# baby_monitor_v0.net
KiCad netlist of a schematic drawn in EAGLE
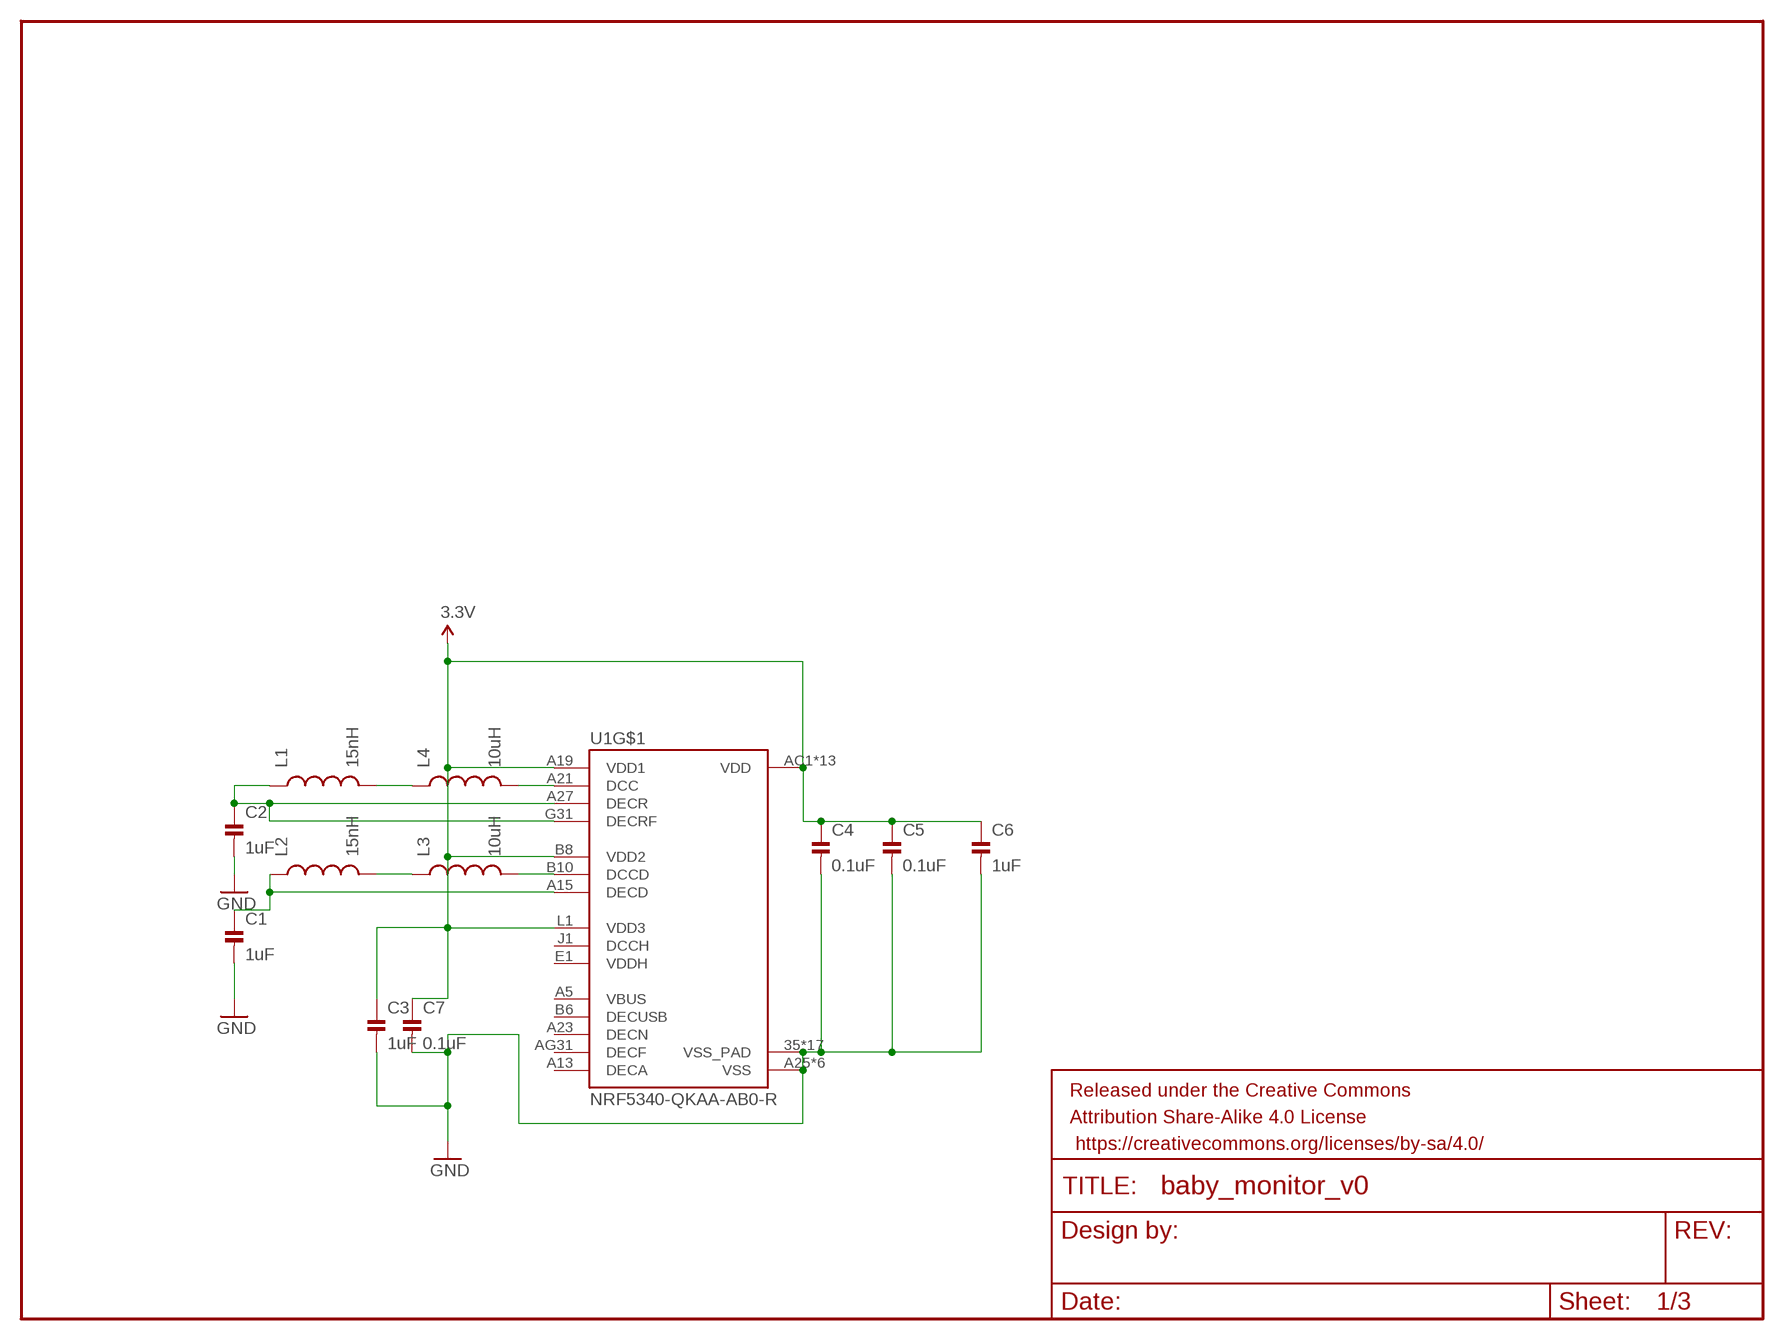
[diagram p0: schematic, sheet 1]
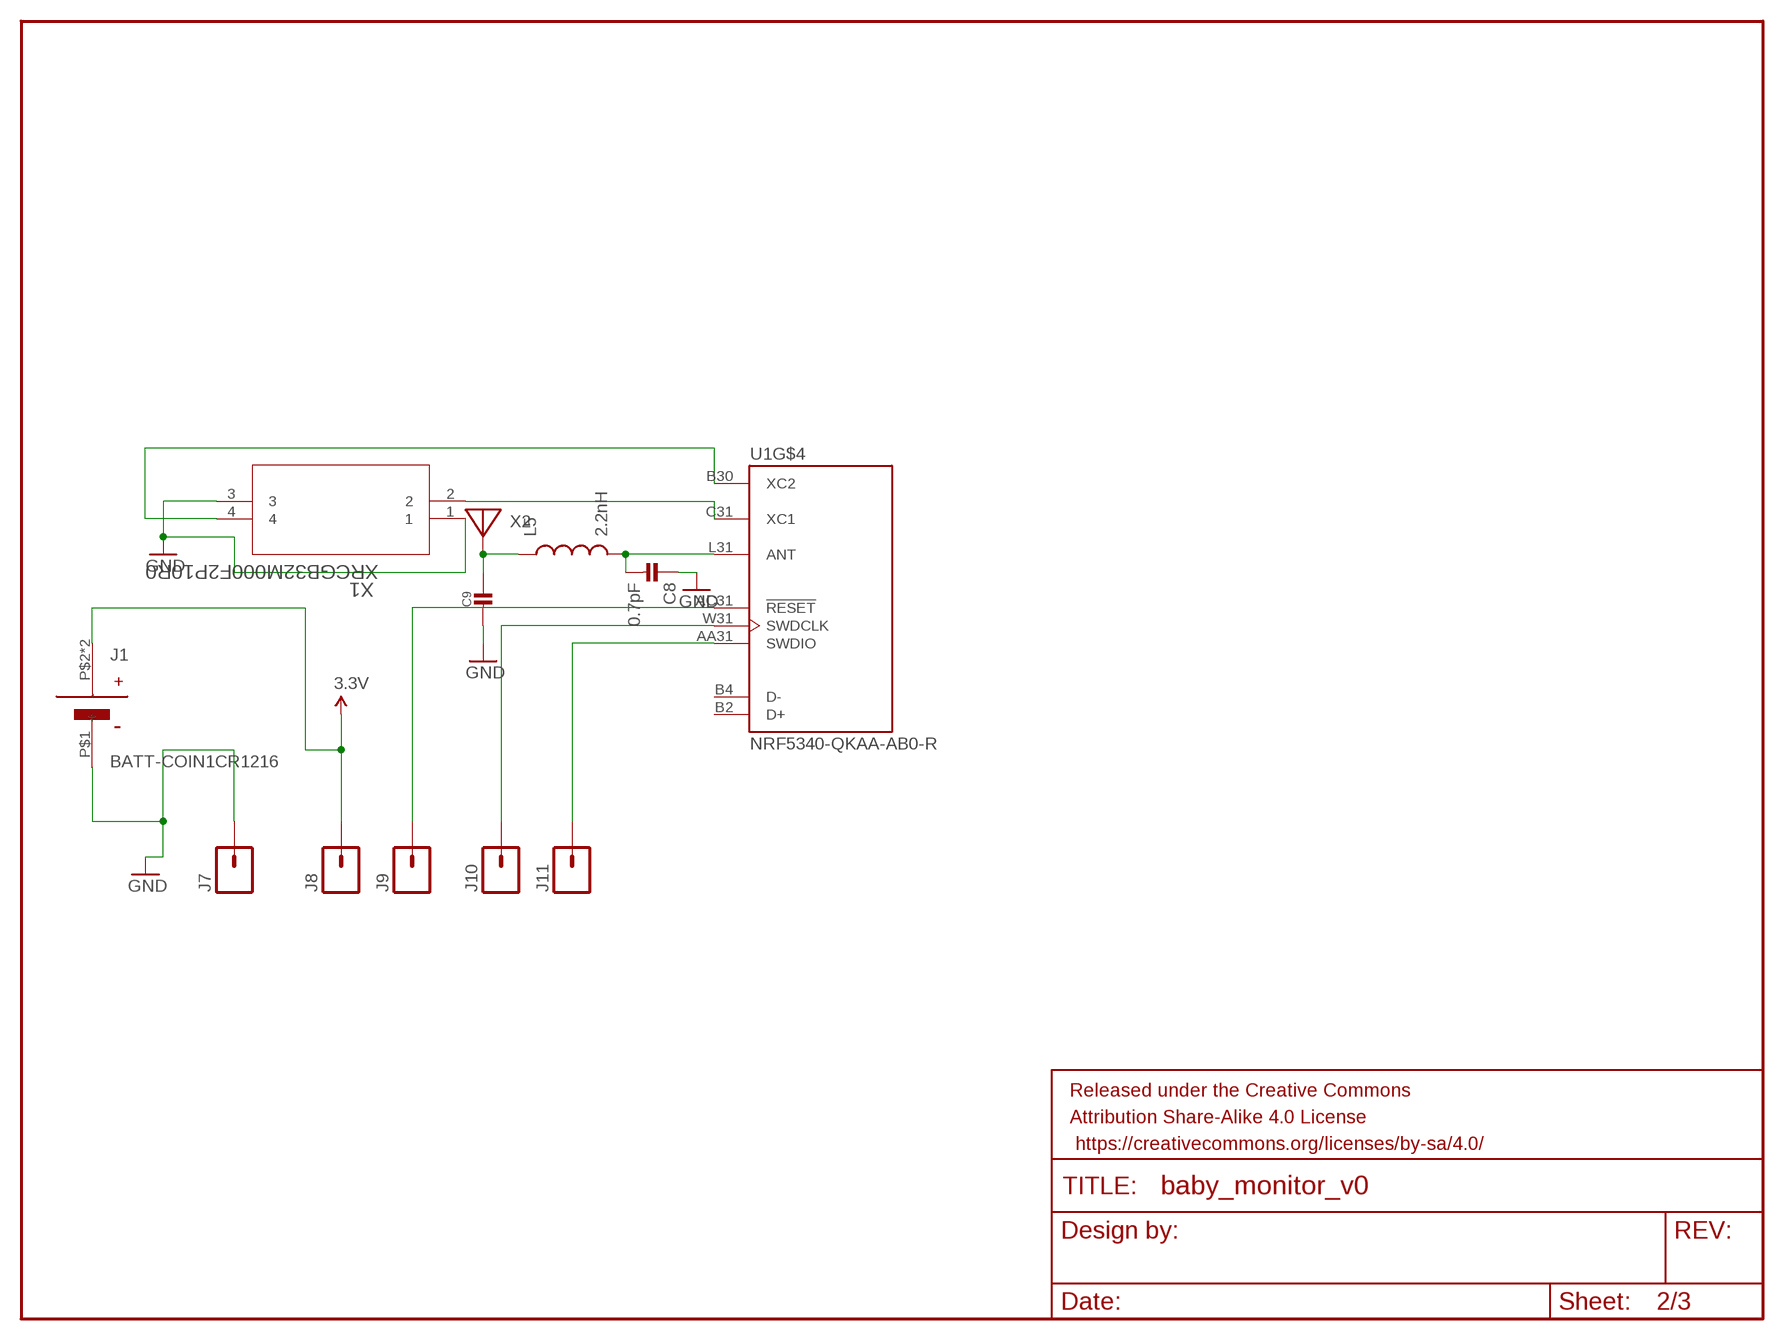
[diagram p1: schematic, sheet 2]
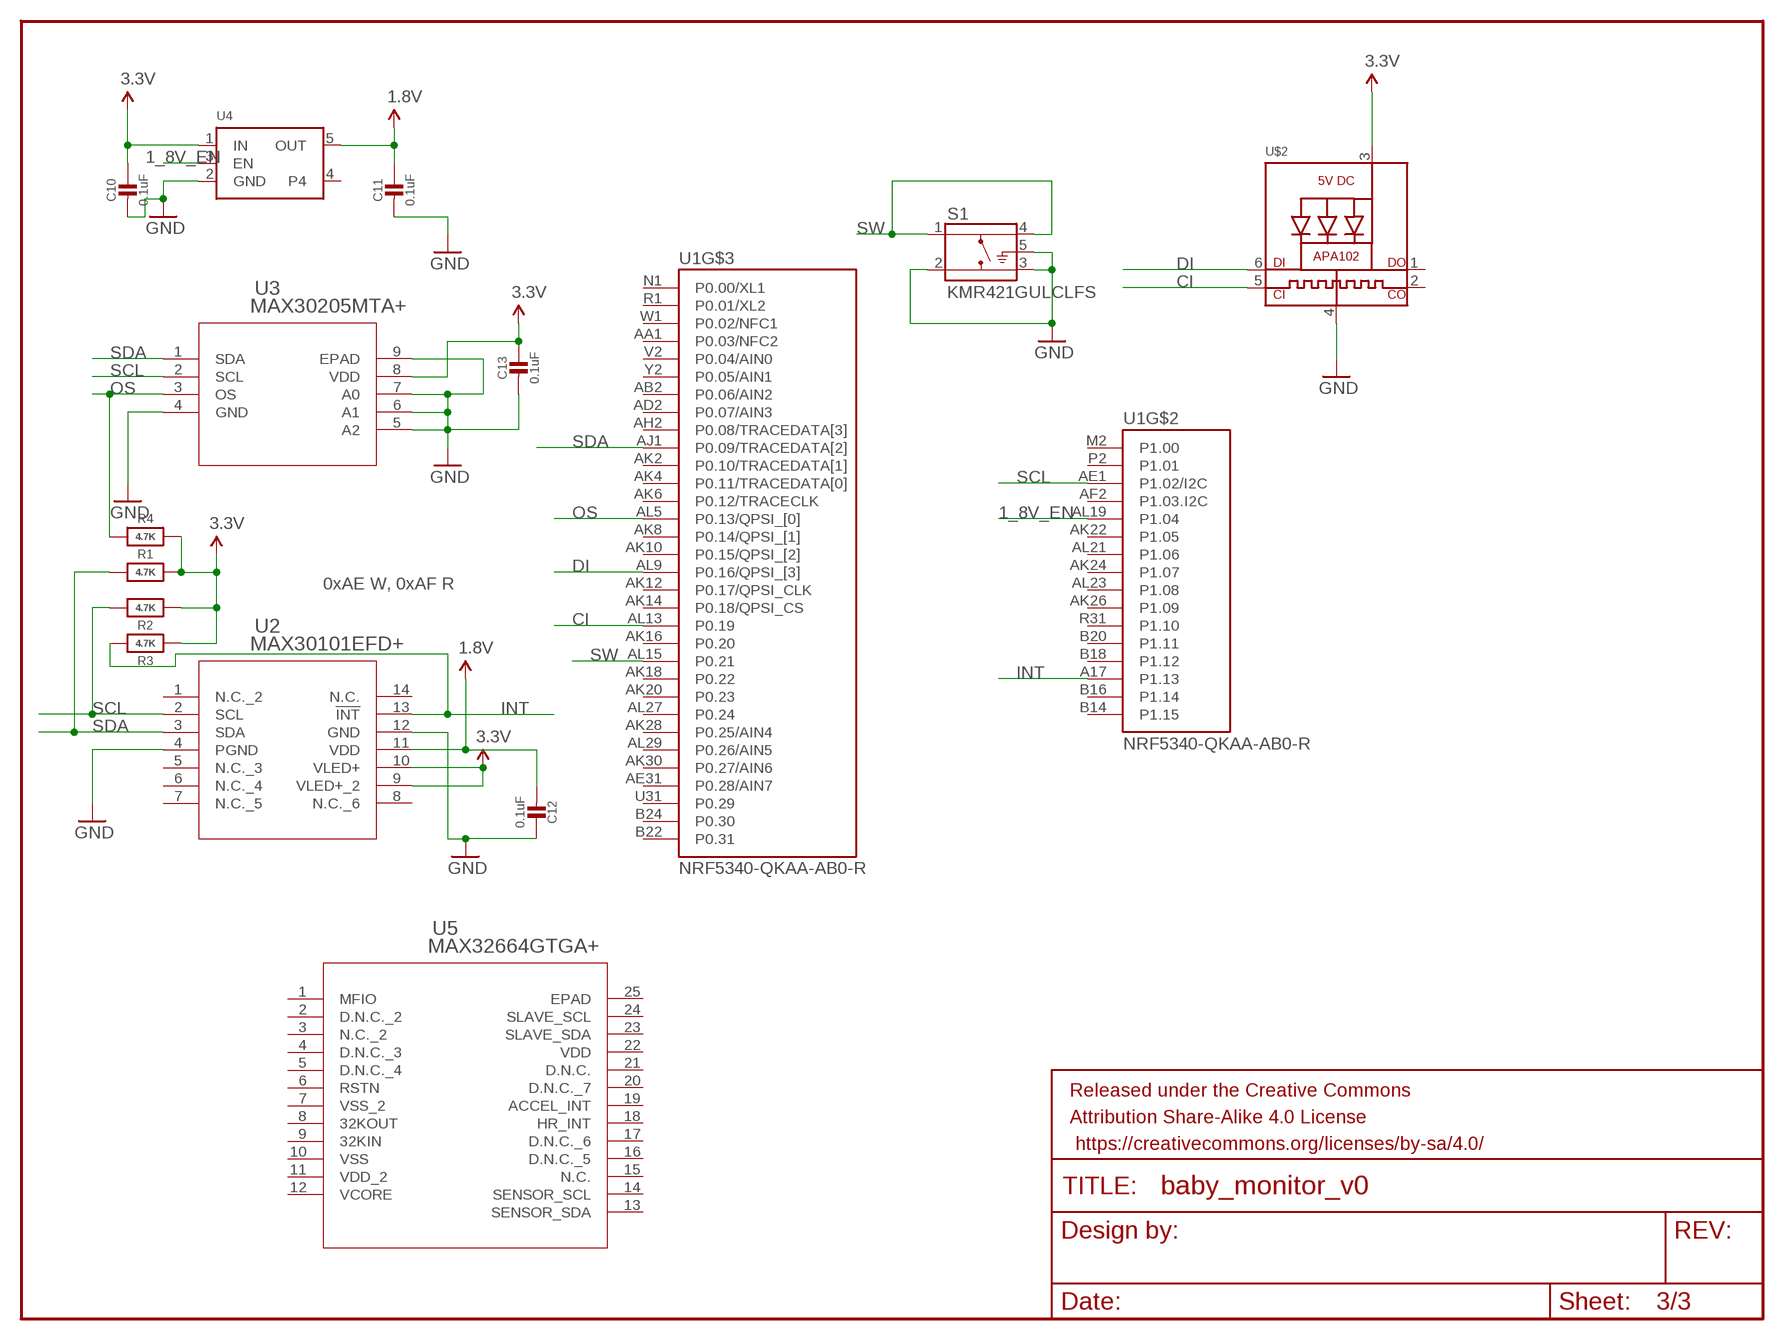
[diagram p2: schematic, sheet 3]

(export (version "E")
  (design (tool "Eeschema 10.0.6"))
  (components
    (comp (ref "C8")
      (value "0.7pF")
      (footprint "eagle-import:MICROBUILDER__0402MP")
      (libsource (lib "eagle-import") (part "MICROBUILDER_CAP_CERAMIC_0402MP"))
    )
    (comp (ref "C9")
      (value "MICROBUILDER_CAP_CERAMIC_0402MP")
      (footprint "eagle-import:MICROBUILDER__0402MP")
      (libsource (lib "eagle-import") (part "graftel-internal-ic_MICROBUILDER_CAP_CERAMIC_0402MP"))
    )
    (comp (ref "FRAME3")
      (value "FRAME-LETTERNO_PACKAGE")
      (footprint "eagle-import:DUMMY")
      (fields (field (name "DESIGNER") "Nobody"))
      (libsource (lib "eagle-import") (part "FRAME-LETTERNO_PACKAGE"))
    )
    (comp (ref "J1")
      (value "BATT-COIN1CR1216")
      (footprint "eagle-import:BC-2017-TR")
      (libsource (lib "eagle-import") (part "BATT-COIN1CR1216"))
    )
    (comp (ref "J7")
      (value "M01TINY")
      (footprint "eagle-import:1X01_TINY")
      (libsource (lib "eagle-import") (part "M01TINY"))
    )
    (comp (ref "J8")
      (value "M01TINY")
      (footprint "eagle-import:1X01_TINY")
      (libsource (lib "eagle-import") (part "M01TINY"))
    )
    (comp (ref "J9")
      (value "M01TINY")
      (footprint "eagle-import:1X01_TINY")
      (libsource (lib "eagle-import") (part "M01TINY"))
    )
    (comp (ref "J10")
      (value "M01TINY")
      (footprint "eagle-import:1X01_TINY")
      (libsource (lib "eagle-import") (part "M01TINY"))
    )
    (comp (ref "J11")
      (value "M01TINY")
      (footprint "eagle-import:1X01_TINY")
      (libsource (lib "eagle-import") (part "M01TINY"))
    )
    (comp (ref "L5")
      (value "2.2nH")
      (footprint "eagle-import:NORDIC_MISC_RESC0402_N")
      (libsource (lib "eagle-import") (part "NORDIC_MISC_INDUCTOR_0402_N"))
    )
    (comp (ref "U1")
      (value "NRF5340-QKAA-AB0-R")
      (footprint "eagle-import:XCVR_NRF5340-QKAA-AB0-R")
      (fields (field (name "MF") "Nordic Semiconductor") (field (name "MP") "nRF5340-QKAA-AB0-R"))
      (libsource (lib "eagle-import") (part "NRF5340-QKAA-AB0-R"))
    )
    (comp (ref "X1")
      (value "XRCGB32M000F2P10R0")
      (footprint "eagle-import:XTAL_SON4_1P6X2P0_MUR")
      (fields (field (name "DIGIKEY_PART") "490-14308-1-ND"))
      (libsource (lib "eagle-import") (part "XRCGB32M000F2P10R0"))
    )
    (comp (ref "X2")
      (value "ADAFRUIT_WIRELESS_ANTENNA_JOHANSON_2450AT18B100")
      (footprint "eagle-import:ADAFRUIT_WIRELESS_ANT_2450AT18B100")
      (fields (field (name "DIGIKEY_PART") "712-1006-1-ND"))
      (libsource (lib "eagle-import") (part "ADAFRUIT_WIRELESS_ANTENNA_JOHANSON_2450AT18B100"))
    )
    (comp (ref "C10")
      (value "0.1uF")
      (footprint "eagle-import:MICROBUILDER__0402MP")
      (libsource (lib "eagle-import") (part "MICROBUILDER_CAP_CERAMIC_0402MP"))
    )
    (comp (ref "C11")
      (value "0.1uF")
      (footprint "eagle-import:MICROBUILDER__0402MP")
      (libsource (lib "eagle-import") (part "MICROBUILDER_CAP_CERAMIC_0402MP"))
    )
    (comp (ref "C12")
      (value "0.1uF")
      (footprint "eagle-import:MICROBUILDER__0402MP")
      (libsource (lib "eagle-import") (part "MICROBUILDER_CAP_CERAMIC_0402MP"))
    )
    (comp (ref "C13")
      (value "0.1uF")
      (footprint "eagle-import:MICROBUILDER__0402MP")
      (libsource (lib "eagle-import") (part "MICROBUILDER_CAP_CERAMIC_0402MP"))
    )
    (comp (ref "FRAME2")
      (value "FRAME-LETTERNO_PACKAGE")
      (footprint "eagle-import:DUMMY")
      (fields (field (name "DESIGNER") "Nobody"))
      (libsource (lib "eagle-import") (part "FRAME-LETTERNO_PACKAGE"))
    )
    (comp (ref "R1")
      (value "4.7K")
      (footprint "eagle-import:MICROBUILDER__0402MP")
      (libsource (lib "eagle-import") (part "MICROBUILDER_RESISTOR_0402MP"))
    )
    (comp (ref "R2")
      (value "4.7K")
      (footprint "eagle-import:MICROBUILDER__0402MP")
      (libsource (lib "eagle-import") (part "MICROBUILDER_RESISTOR_0402MP"))
    )
    (comp (ref "R3")
      (value "4.7K")
      (footprint "eagle-import:MICROBUILDER__0402MP")
      (libsource (lib "eagle-import") (part "MICROBUILDER_RESISTOR_0402MP"))
    )
    (comp (ref "R4")
      (value "4.7K")
      (footprint "eagle-import:MICROBUILDER__0402MP")
      (libsource (lib "eagle-import") (part "MICROBUILDER_RESISTOR_0402MP"))
    )
    (comp (ref "S1")
      (value "KMR421GULCLFS")
      (footprint "eagle-import:SW_KMR421GULCLFS")
      (fields (field (name "DIGI-KEY_PART_NUMBER") "CKN12152CT-ND") (field (name "MF") "C&K"))
      (libsource (lib "eagle-import") (part "KMR421GULCLFS"))
    )
    (comp (ref "U$2")
      (value "MICROBUILDER_APA1022020")
      (footprint "eagle-import:MICROBUILDER_APA102_2020")
      (libsource (lib "eagle-import") (part "MICROBUILDER_APA1022020"))
    )
    (comp (ref "U2")
      (value "MAX30101EFD+")
      (footprint "eagle-import:21-0880B_MXM")
      (libsource (lib "eagle-import") (part "MAX30101EFD+"))
    )
    (comp (ref "U3")
      (value "MAX30205MTA+")
      (footprint "eagle-import:21-0137_T833+2_MXM")
      (fields (field (name "COPYRIGHT") "Copyright (C) 2018 Accelerated Designs. All rights reserved"))
      (libsource (lib "eagle-import") (part "MAX30205MTA+"))
    )
    (comp (ref "U4")
      (value "MICROBUILDER_VREG_SOT23-5")
      (footprint "eagle-import:MICROBUILDER_SOT23-5")
      (libsource (lib "eagle-import") (part "MICROBUILDER_VREG_SOT23-5"))
    )
    (comp (ref "U5")
      (value "MAX32664GTGA+")
      (footprint "eagle-import:21-100264_90-100089_MXM")
      (fields (field (name "COPYRIGHT") "Copyright (C) 2018 Accelerated Designs. All rights reserved"))
      (libsource (lib "eagle-import") (part "MAX32664GTGA+"))
    )
    (comp (ref "C1")
      (value "1uF")
      (footprint "eagle-import:MICROBUILDER__0402MP")
      (libsource (lib "eagle-import") (part "MICROBUILDER_CAP_CERAMIC_0402MP"))
    )
    (comp (ref "C2")
      (value "1uF")
      (footprint "eagle-import:MICROBUILDER__0402MP")
      (libsource (lib "eagle-import") (part "MICROBUILDER_CAP_CERAMIC_0402MP"))
    )
    (comp (ref "C3")
      (value "1uF")
      (footprint "eagle-import:MICROBUILDER__0402MP")
      (libsource (lib "eagle-import") (part "MICROBUILDER_CAP_CERAMIC_0402MP"))
    )
    (comp (ref "C4")
      (value "0.1uF")
      (footprint "eagle-import:MICROBUILDER__0402MP")
      (libsource (lib "eagle-import") (part "MICROBUILDER_CAP_CERAMIC_0402MP"))
    )
    (comp (ref "C5")
      (value "0.1uF")
      (footprint "eagle-import:MICROBUILDER__0402MP")
      (libsource (lib "eagle-import") (part "MICROBUILDER_CAP_CERAMIC_0402MP"))
    )
    (comp (ref "C6")
      (value "1uF")
      (footprint "eagle-import:MICROBUILDER__0402MP")
      (libsource (lib "eagle-import") (part "MICROBUILDER_CAP_CERAMIC_0402MP"))
    )
    (comp (ref "C7")
      (value "0.1uF")
      (footprint "eagle-import:MICROBUILDER__0402MP")
      (libsource (lib "eagle-import") (part "MICROBUILDER_CAP_CERAMIC_0402MP"))
    )
    (comp (ref "FRAME1")
      (value "FRAME-LETTERNO_PACKAGE")
      (footprint "eagle-import:DUMMY")
      (fields (field (name "DESIGNER") "Nobody"))
      (libsource (lib "eagle-import") (part "FRAME-LETTERNO_PACKAGE"))
    )
    (comp (ref "L1")
      (value "15nH")
      (footprint "eagle-import:NORDIC_MISC_RESC0402_N")
      (libsource (lib "eagle-import") (part "NORDIC_MISC_INDUCTOR_0402_N"))
    )
    (comp (ref "L2")
      (value "15nH")
      (footprint "eagle-import:NORDIC_MISC_RESC0402_N")
      (libsource (lib "eagle-import") (part "NORDIC_MISC_INDUCTOR_0402_N"))
    )
    (comp (ref "L3")
      (value "10uH")
      (footprint "eagle-import:NORDIC_MISC_RESC0603_N")
      (libsource (lib "eagle-import") (part "NORDIC_MISC_INDUCTOR_0603_N"))
    )
    (comp (ref "L4")
      (value "10uH")
      (footprint "eagle-import:NORDIC_MISC_RESC0603_N")
      (libsource (lib "eagle-import") (part "NORDIC_MISC_INDUCTOR_0603_N"))
    )
  )
  (nets
    (net (code "1") (name "1.8V") (class "Default")
      (node (ref "C11") (pin "1") (pinfunction "1_1") (pintype "passive"))
      (node (ref "C12") (pin "2") (pinfunction "2_2") (pintype "passive"))
      (node (ref "U2") (pin "11") (pinfunction "VDD_11") (pintype "power_in"))
      (node (ref "U4") (pin "5") (pinfunction "OUT_5") (pintype "power_in"))
    )
    (net (code "2") (name "1_8V_EN") (class "Default")
      (node (ref "U1") (pin "AL19") (pinfunction "P1.04_AL19") (pintype "bidirectional"))
      (node (ref "U4") (pin "3") (pinfunction "EN_3") (pintype "input"))
    )
    (net (code "3") (name "3.3V") (class "Default")
      (node (ref "C10") (pin "1") (pinfunction "1_1") (pintype "passive"))
      (node (ref "C13") (pin "1") (pinfunction "1_1") (pintype "passive"))
      (node (ref "C3") (pin "1") (pinfunction "1_1") (pintype "passive"))
      (node (ref "C4") (pin "1") (pinfunction "1_1") (pintype "passive"))
      (node (ref "C5") (pin "1") (pinfunction "1_1") (pintype "passive"))
      (node (ref "C6") (pin "1") (pinfunction "1_1") (pintype "passive"))
      (node (ref "C7") (pin "1") (pinfunction "1_1") (pintype "passive"))
      (node (ref "J1") (pin "P$2") (pinfunction "+_P$2") (pintype "bidirectional"))
      (node (ref "J1") (pin "P$3") (pinfunction "+_P$3") (pintype "bidirectional"))
      (node (ref "J8") (pin "P$1") (pinfunction "1_P$1") (pintype "passive"))
      (node (ref "R1") (pin "2") (pinfunction "2_2") (pintype "passive"))
      (node (ref "R2") (pin "1") (pinfunction "1_1") (pintype "passive"))
      (node (ref "R3") (pin "1") (pinfunction "1_1") (pintype "passive"))
      (node (ref "R4") (pin "2") (pinfunction "2_2") (pintype "passive"))
      (node (ref "U$2") (pin "3") (pinfunction "VDD_3") (pintype "power_in"))
      (node (ref "U1") (pin "A19") (pinfunction "VDD1_A19") (pintype "power_in"))
      (node (ref "U1") (pin "AC1") (pinfunction "VDD_AC1") (pintype "power_in"))
      (node (ref "U1") (pin "AG1") (pinfunction "VDD_AG1") (pintype "power_in"))
      (node (ref "U1") (pin "AJ31") (pinfunction "VDD_AJ31") (pintype "power_in"))
      (node (ref "U1") (pin "AL11") (pinfunction "VDD_AL11") (pintype "power_in"))
      (node (ref "U1") (pin "AL17") (pinfunction "VDD_AL17") (pintype "power_in"))
      (node (ref "U1") (pin "AL25") (pinfunction "VDD_AL25") (pintype "power_in"))
      (node (ref "U1") (pin "AL3") (pinfunction "VDD_AL3") (pintype "power_in"))
      (node (ref "U1") (pin "AL7") (pinfunction "VDD_AL7") (pintype "power_in"))
      (node (ref "U1") (pin "B28") (pinfunction "VDD_B28") (pintype "power_in"))
      (node (ref "U1") (pin "B8") (pinfunction "VDD2_B8") (pintype "power_in"))
      (node (ref "U1") (pin "C1") (pinfunction "VDD_C1") (pintype "power_in"))
      (node (ref "U1") (pin "E31") (pinfunction "VDD_E31") (pintype "power_in"))
      (node (ref "U1") (pin "L1") (pinfunction "VDD3_L1") (pintype "power_in"))
      (node (ref "U1") (pin "N31") (pinfunction "VDD_N31") (pintype "power_in"))
      (node (ref "U1") (pin "U1") (pinfunction "VDD_U1") (pintype "power_in"))
      (node (ref "U2") (pin "10") (pinfunction "VLED+_10") (pintype "passive"))
      (node (ref "U2") (pin "9") (pinfunction "VLED+_2_9") (pintype "passive"))
      (node (ref "U3") (pin "8") (pinfunction "VDD_8") (pintype "power_in"))
      (node (ref "U4") (pin "1") (pinfunction "IN_1") (pintype "power_in"))
    )
    (net (code "4") (name "CI") (class "Default")
      (node (ref "U$2") (pin "5") (pinfunction "CKI_5") (pintype "input"))
      (node (ref "U1") (pin "AL13") (pinfunction "P0.19_AL13") (pintype "bidirectional"))
    )
    (net (code "5") (name "DCCH") (class "Default")
      (node (ref "U1") (pin "J1") (pinfunction "DCCH_J1") (pintype "power_in"))
    )
    (net (code "6") (name "DECA") (class "Default")
      (node (ref "U1") (pin "A13") (pinfunction "DECA_A13") (pintype "power_in"))
    )
    (net (code "7") (name "DECF") (class "Default")
      (node (ref "U1") (pin "AG31") (pinfunction "DECF_AG31") (pintype "power_in"))
    )
    (net (code "8") (name "DECN") (class "Default")
      (node (ref "U1") (pin "A23") (pinfunction "DECN_A23") (pintype "power_in"))
    )
    (net (code "9") (name "DECUSB") (class "Default")
      (node (ref "U1") (pin "B6") (pinfunction "DECUSB_B6") (pintype "power_in"))
    )
    (net (code "10") (name "DI") (class "Default")
      (node (ref "U$2") (pin "6") (pinfunction "DI_6") (pintype "input"))
      (node (ref "U1") (pin "AL9") (pinfunction "P0.16/QPSI_[3]_AL9") (pintype "bidirectional"))
    )
    (net (code "11") (name "EPAD") (class "Default")
      (node (ref "U5") (pin "25") (pinfunction "EPAD_25") (pintype "power_in"))
    )
    (net (code "12") (name "GND") (class "Default")
      (node (ref "C1") (pin "2") (pinfunction "2_2") (pintype "passive"))
      (node (ref "C10") (pin "2") (pinfunction "2_2") (pintype "passive"))
      (node (ref "C11") (pin "2") (pinfunction "2_2") (pintype "passive"))
      (node (ref "C12") (pin "1") (pinfunction "1_1") (pintype "passive"))
      (node (ref "C13") (pin "2") (pinfunction "2_2") (pintype "passive"))
      (node (ref "C2") (pin "2") (pinfunction "2_2") (pintype "passive"))
      (node (ref "C3") (pin "2") (pinfunction "2_2") (pintype "passive"))
      (node (ref "C4") (pin "2") (pinfunction "2_2") (pintype "passive"))
      (node (ref "C5") (pin "2") (pinfunction "2_2") (pintype "passive"))
      (node (ref "C6") (pin "2") (pinfunction "2_2") (pintype "passive"))
      (node (ref "C7") (pin "2") (pinfunction "2_2") (pintype "passive"))
      (node (ref "C8") (pin "1") (pinfunction "1_1") (pintype "passive"))
      (node (ref "C9") (pin "2") (pinfunction "2_2") (pintype "passive"))
      (node (ref "J1") (pin "P$1") (pinfunction "-_P$1") (pintype "bidirectional"))
      (node (ref "J7") (pin "P$1") (pinfunction "1_P$1") (pintype "passive"))
      (node (ref "S1") (pin "2") (pinfunction "2_2") (pintype "passive"))
      (node (ref "S1") (pin "3") (pinfunction "3_3") (pintype "passive"))
      (node (ref "S1") (pin "5") (pinfunction "G_5") (pintype "power_in"))
      (node (ref "U$2") (pin "4") (pinfunction "GND_4") (pintype "power_in"))
      (node (ref "U1") (pin "104") (pinfunction "VSS_PAD_104") (pintype "power_in"))
      (node (ref "U1") (pin "35") (pinfunction "VSS_PAD_35") (pintype "power_in"))
      (node (ref "U1") (pin "36") (pinfunction "VSS_PAD_36") (pintype "power_in"))
      (node (ref "U1") (pin "37") (pinfunction "VSS_PAD_37") (pintype "power_in"))
      (node (ref "U1") (pin "38") (pinfunction "VSS_PAD_38") (pintype "power_in"))
      (node (ref "U1") (pin "39") (pinfunction "VSS_PAD_39") (pintype "power_in"))
      (node (ref "U1") (pin "40") (pinfunction "VSS_PAD_40") (pintype "power_in"))
      (node (ref "U1") (pin "41") (pinfunction "VSS_PAD_41") (pintype "power_in"))
      (node (ref "U1") (pin "43") (pinfunction "VSS_PAD_43") (pintype "power_in"))
      (node (ref "U1") (pin "44") (pinfunction "VSS_PAD_44") (pintype "power_in"))
      (node (ref "U1") (pin "45") (pinfunction "VSS_PAD_45") (pintype "power_in"))
      (node (ref "U1") (pin "46") (pinfunction "VSS_PAD_46") (pintype "power_in"))
      (node (ref "U1") (pin "47") (pinfunction "VSS_PAD_47") (pintype "power_in"))
      (node (ref "U1") (pin "48") (pinfunction "VSS_PAD_48") (pintype "power_in"))
      (node (ref "U1") (pin "49") (pinfunction "VSS_PAD_49") (pintype "power_in"))
      (node (ref "U1") (pin "50") (pinfunction "VSS_PAD_50") (pintype "power_in"))
      (node (ref "U1") (pin "51") (pinfunction "VSS_PAD_51") (pintype "power_in"))
      (node (ref "U1") (pin "A25") (pinfunction "VSS_A25") (pintype "power_in"))
      (node (ref "U1") (pin "B12") (pinfunction "VSS_B12") (pintype "power_in"))
      (node (ref "U1") (pin "B26") (pinfunction "VSS_B26") (pintype "power_in"))
      (node (ref "U1") (pin "G1") (pinfunction "VSS_G1") (pintype "power_in"))
      (node (ref "U1") (pin "H2") (pinfunction "VSS_H2") (pintype "power_in"))
      (node (ref "U1") (pin "J31") (pinfunction "VSS_J31") (pintype "power_in"))
      (node (ref "U2") (pin "12") (pinfunction "GND_12") (pintype "passive"))
      (node (ref "U2") (pin "4") (pinfunction "PGND_4") (pintype "passive"))
      (node (ref "U3") (pin "4") (pinfunction "GND_4") (pintype "passive"))
      (node (ref "U3") (pin "5") (pinfunction "A2_5") (pintype "bidirectional"))
      (node (ref "U3") (pin "6") (pinfunction "A1_6") (pintype "bidirectional"))
      (node (ref "U3") (pin "7") (pinfunction "A0_7") (pintype "bidirectional"))
      (node (ref "U3") (pin "9") (pinfunction "EPAD_9") (pintype "passive"))
      (node (ref "U4") (pin "2") (pinfunction "GND_2") (pintype "power_in"))
      (node (ref "X1") (pin "1") (pinfunction "1_1") (pintype "passive"))
      (node (ref "X1") (pin "3") (pinfunction "3_3") (pintype "passive"))
    )
    (net (code "13") (name "INT") (class "Default")
      (node (ref "R3") (pin "2") (pinfunction "2_2") (pintype "passive"))
      (node (ref "U1") (pin "A17") (pinfunction "P1.13_A17") (pintype "bidirectional"))
      (node (ref "U2") (pin "13") (pinfunction "~{INT}_13") (pintype "passive"))
    )
    (net (code "14") (name "Net-(J9-1)") (class "Default")
      (node (ref "J9") (pin "P$1") (pinfunction "1_P$1") (pintype "passive"))
      (node (ref "U1") (pin "AC31") (pinfunction "~{RESET}_AC31") (pintype "input"))
    )
    (net (code "15") (name "Net-(J10-1)") (class "Default")
      (node (ref "J10") (pin "P$1") (pinfunction "1_P$1") (pintype "passive"))
      (node (ref "U1") (pin "W31") (pinfunction "SWDCLK_W31") (pintype "input"))
    )
    (net (code "16") (name "Net-(J11-1)") (class "Default")
      (node (ref "J11") (pin "P$1") (pinfunction "1_P$1") (pintype "passive"))
      (node (ref "U1") (pin "AA31") (pinfunction "SWDIO_AA31") (pintype "bidirectional"))
    )
    (net (code "17") (name "Net-(L1-Pad2)") (class "Default")
      (node (ref "L1") (pin "2") (pinfunction "2_2") (pintype "passive"))
      (node (ref "L4") (pin "1") (pinfunction "1_1") (pintype "passive"))
    )
    (net (code "18") (name "Net-(L2-Pad2)") (class "Default")
      (node (ref "L2") (pin "2") (pinfunction "2_2") (pintype "passive"))
      (node (ref "L3") (pin "1") (pinfunction "1_1") (pintype "passive"))
    )
    (net (code "19") (name "Net-(U1A-DCC)") (class "Default")
      (node (ref "L4") (pin "2") (pinfunction "2_2") (pintype "passive"))
      (node (ref "U1") (pin "A21") (pinfunction "DCC_A21") (pintype "output"))
    )
    (net (code "20") (name "Net-(U1A-DCCD)") (class "Default")
      (node (ref "L3") (pin "2") (pinfunction "2_2") (pintype "passive"))
      (node (ref "U1") (pin "B10") (pinfunction "DCCD_B10") (pintype "power_in"))
    )
    (net (code "21") (name "Net-(U1A-DECD)") (class "Default")
      (node (ref "C1") (pin "1") (pinfunction "1_1") (pintype "passive"))
      (node (ref "L2") (pin "1") (pinfunction "1_1") (pintype "passive"))
      (node (ref "U1") (pin "A15") (pinfunction "DECD_A15") (pintype "power_in"))
    )
    (net (code "22") (name "Net-(U1A-DECR)") (class "Default")
      (node (ref "C2") (pin "1") (pinfunction "1_1") (pintype "passive"))
      (node (ref "L1") (pin "1") (pinfunction "1_1") (pintype "passive"))
      (node (ref "U1") (pin "A27") (pinfunction "DECR_A27") (pintype "power_in"))
      (node (ref "U1") (pin "G31") (pinfunction "DECRF_G31") (pintype "power_in"))
    )
    (net (code "23") (name "Net-(U1D-ANT)") (class "Default")
      (node (ref "C8") (pin "2") (pinfunction "2_2") (pintype "passive"))
      (node (ref "L5") (pin "2") (pinfunction "2_2") (pintype "passive"))
      (node (ref "U1") (pin "L31") (pinfunction "ANT_L31") (pintype "bidirectional"))
    )
    (net (code "24") (name "Net-(U1D-XC1)") (class "Default")
      (node (ref "U1") (pin "C31") (pinfunction "XC1_C31") (pintype "input"))
      (node (ref "X1") (pin "2") (pinfunction "2_2") (pintype "passive"))
    )
    (net (code "25") (name "Net-(U1D-XC2)") (class "Default")
      (node (ref "U1") (pin "B30") (pinfunction "XC2_B30") (pintype "output"))
      (node (ref "X1") (pin "4") (pinfunction "4_4") (pintype "passive"))
    )
    (net (code "26") (name "Net-(X2-P$1)") (class "Default")
      (node (ref "C9") (pin "1") (pinfunction "1_1") (pintype "passive"))
      (node (ref "L5") (pin "1") (pinfunction "1_1") (pintype "passive"))
      (node (ref "X2") (pin "FP") (pinfunction "P$1_FP") (pintype "passive"))
    )
    (net (code "27") (name "OS") (class "Default")
      (node (ref "R4") (pin "1") (pinfunction "1_1") (pintype "passive"))
      (node (ref "U1") (pin "AL5") (pinfunction "P0.13/QPSI_[0]_AL5") (pintype "bidirectional"))
      (node (ref "U3") (pin "3") (pinfunction "OS_3") (pintype "passive"))
    )
    (net (code "28") (name "SCL") (class "Default")
      (node (ref "R2") (pin "2") (pinfunction "2_2") (pintype "passive"))
      (node (ref "U1") (pin "AE1") (pinfunction "P1.02/I2C_AE1") (pintype "bidirectional"))
      (node (ref "U2") (pin "2") (pinfunction "SCL_2") (pintype "passive"))
      (node (ref "U3") (pin "2") (pinfunction "SCL_2") (pintype "passive"))
    )
    (net (code "29") (name "SDA") (class "Default")
      (node (ref "R1") (pin "1") (pinfunction "1_1") (pintype "passive"))
      (node (ref "U1") (pin "AJ1") (pinfunction "P0.09/TRACEDATA[2]_AJ1") (pintype "bidirectional"))
      (node (ref "U2") (pin "3") (pinfunction "SDA_3") (pintype "passive"))
      (node (ref "U3") (pin "1") (pinfunction "SDA_1") (pintype "passive"))
    )
    (net (code "30") (name "SW") (class "Default")
      (node (ref "S1") (pin "1") (pinfunction "1_1") (pintype "passive"))
      (node (ref "S1") (pin "4") (pinfunction "4_4") (pintype "passive"))
      (node (ref "U1") (pin "AL15") (pinfunction "P0.21_AL15") (pintype "bidirectional"))
    )
    (net (code "31") (name "VBUS") (class "Default")
      (node (ref "U1") (pin "A5") (pinfunction "VBUS_A5") (pintype "power_in"))
    )
    (net (code "32") (name "VCORE") (class "Default")
      (node (ref "U5") (pin "12") (pinfunction "VCORE_12") (pintype "power_in"))
    )
    (net (code "33") (name "VDD") (class "Default")
      (node (ref "U5") (pin "22") (pinfunction "VDD_22") (pintype "power_in"))
    )
    (net (code "34") (name "VDDH") (class "Default")
      (node (ref "U1") (pin "E1") (pinfunction "VDDH_E1") (pintype "power_in"))
    )
    (net (code "35") (name "VDD_2") (class "Default")
      (node (ref "U5") (pin "11") (pinfunction "VDD_2_11") (pintype "power_in"))
    )
    (net (code "36") (name "VSS") (class "Default")
      (node (ref "U5") (pin "10") (pinfunction "VSS_10") (pintype "power_in"))
    )
    (net (code "37") (name "VSS_2") (class "Default")
      (node (ref "U5") (pin "7") (pinfunction "VSS_2_7") (pintype "power_in"))
    )
    (net (code "38") (name "unconnected-(U$2-CKO-Pad2)") (class "Default")
      (node (ref "U$2") (pin "2") (pinfunction "CKO_2") (pintype "output"))
    )
    (net (code "39") (name "unconnected-(U$2-DO-Pad1)") (class "Default")
      (node (ref "U$2") (pin "1") (pinfunction "DO_1") (pintype "output"))
    )
    (net (code "40") (name "unconnected-(U1B-P1.00-PadM2)") (class "Default")
      (node (ref "U1") (pin "M2") (pinfunction "P1.00_M2") (pintype "bidirectional"))
    )
    (net (code "41") (name "unconnected-(U1B-P1.01-PadP2)") (class "Default")
      (node (ref "U1") (pin "P2") (pinfunction "P1.01_P2") (pintype "bidirectional"))
    )
    (net (code "42") (name "unconnected-(U1B-P1.03.I2C-PadAF2)") (class "Default")
      (node (ref "U1") (pin "AF2") (pinfunction "P1.03.I2C_AF2") (pintype "bidirectional"))
    )
    (net (code "43") (name "unconnected-(U1B-P1.05-PadAK22)") (class "Default")
      (node (ref "U1") (pin "AK22") (pinfunction "P1.05_AK22") (pintype "bidirectional"))
    )
    (net (code "44") (name "unconnected-(U1B-P1.06-PadAL21)") (class "Default")
      (node (ref "U1") (pin "AL21") (pinfunction "P1.06_AL21") (pintype "bidirectional"))
    )
    (net (code "45") (name "unconnected-(U1B-P1.07-PadAK24)") (class "Default")
      (node (ref "U1") (pin "AK24") (pinfunction "P1.07_AK24") (pintype "bidirectional"))
    )
    (net (code "46") (name "unconnected-(U1B-P1.08-PadAL23)") (class "Default")
      (node (ref "U1") (pin "AL23") (pinfunction "P1.08_AL23") (pintype "bidirectional"))
    )
    (net (code "47") (name "unconnected-(U1B-P1.09-PadAK26)") (class "Default")
      (node (ref "U1") (pin "AK26") (pinfunction "P1.09_AK26") (pintype "bidirectional"))
    )
    (net (code "48") (name "unconnected-(U1B-P1.10-PadR31)") (class "Default")
      (node (ref "U1") (pin "R31") (pinfunction "P1.10_R31") (pintype "bidirectional"))
    )
    (net (code "49") (name "unconnected-(U1B-P1.11-PadB20)") (class "Default")
      (node (ref "U1") (pin "B20") (pinfunction "P1.11_B20") (pintype "bidirectional"))
    )
    (net (code "50") (name "unconnected-(U1B-P1.12-PadB18)") (class "Default")
      (node (ref "U1") (pin "B18") (pinfunction "P1.12_B18") (pintype "bidirectional"))
    )
    (net (code "51") (name "unconnected-(U1B-P1.14-PadB16)") (class "Default")
      (node (ref "U1") (pin "B16") (pinfunction "P1.14_B16") (pintype "bidirectional"))
    )
    (net (code "52") (name "unconnected-(U1B-P1.15-PadB14)") (class "Default")
      (node (ref "U1") (pin "B14") (pinfunction "P1.15_B14") (pintype "bidirectional"))
    )
    (net (code "53") (name "unconnected-(U1C-P0.00{slash}XL1-PadN1)") (class "Default")
      (node (ref "U1") (pin "N1") (pinfunction "P0.00/XL1_N1") (pintype "bidirectional"))
    )
    (net (code "54") (name "unconnected-(U1C-P0.01{slash}XL2-PadR1)") (class "Default")
      (node (ref "U1") (pin "R1") (pinfunction "P0.01/XL2_R1") (pintype "bidirectional"))
    )
    (net (code "55") (name "unconnected-(U1C-P0.02{slash}NFC1-PadW1)") (class "Default")
      (node (ref "U1") (pin "W1") (pinfunction "P0.02/NFC1_W1") (pintype "bidirectional"))
    )
    (net (code "56") (name "unconnected-(U1C-P0.03{slash}NFC2-PadAA1)") (class "Default")
      (node (ref "U1") (pin "AA1") (pinfunction "P0.03/NFC2_AA1") (pintype "bidirectional"))
    )
    (net (code "57") (name "unconnected-(U1C-P0.04{slash}AIN0-PadV2)") (class "Default")
      (node (ref "U1") (pin "V2") (pinfunction "P0.04/AIN0_V2") (pintype "bidirectional"))
    )
    (net (code "58") (name "unconnected-(U1C-P0.05{slash}AIN1-PadY2)") (class "Default")
      (node (ref "U1") (pin "Y2") (pinfunction "P0.05/AIN1_Y2") (pintype "bidirectional"))
    )
    (net (code "59") (name "unconnected-(U1C-P0.06{slash}AIN2-PadAB2)") (class "Default")
      (node (ref "U1") (pin "AB2") (pinfunction "P0.06/AIN2_AB2") (pintype "bidirectional"))
    )
    (net (code "60") (name "unconnected-(U1C-P0.07{slash}AIN3-PadAD2)") (class "Default")
      (node (ref "U1") (pin "AD2") (pinfunction "P0.07/AIN3_AD2") (pintype "bidirectional"))
    )
    (net (code "61") (name "unconnected-(U1C-P0.08{slash}TRACEDATA[3]-PadAH2)") (class "Default")
      (node (ref "U1") (pin "AH2") (pinfunction "P0.08/TRACEDATA[3]_AH2") (pintype "bidirectional"))
    )
    (net (code "62") (name "unconnected-(U1C-P0.10{slash}TRACEDATA[1]-PadAK2)") (class "Default")
      (node (ref "U1") (pin "AK2") (pinfunction "P0.10/TRACEDATA[1]_AK2") (pintype "bidirectional"))
    )
    (net (code "63") (name "unconnected-(U1C-P0.11{slash}TRACEDATA[0]-PadAK4)") (class "Default")
      (node (ref "U1") (pin "AK4") (pinfunction "P0.11/TRACEDATA[0]_AK4") (pintype "bidirectional"))
    )
    (net (code "64") (name "unconnected-(U1C-P0.12{slash}TRACECLK-PadAK6)") (class "Default")
      (node (ref "U1") (pin "AK6") (pinfunction "P0.12/TRACECLK_AK6") (pintype "bidirectional"))
    )
    (net (code "65") (name "unconnected-(U1C-P0.14{slash}QPSI_[1]-PadAK8)") (class "Default")
      (node (ref "U1") (pin "AK8") (pinfunction "P0.14/QPSI_[1]_AK8") (pintype "bidirectional"))
    )
    (net (code "66") (name "unconnected-(U1C-P0.15{slash}QPSI_[2]-PadAK10)") (class "Default")
      (node (ref "U1") (pin "AK10") (pinfunction "P0.15/QPSI_[2]_AK10") (pintype "bidirectional"))
    )
    (net (code "67") (name "unconnected-(U1C-P0.17{slash}QPSI_CLK-PadAK12)") (class "Default")
      (node (ref "U1") (pin "AK12") (pinfunction "P0.17/QPSI_CLK_AK12") (pintype "bidirectional"))
    )
    (net (code "68") (name "unconnected-(U1C-P0.18{slash}QPSI_CS-PadAK14)") (class "Default")
      (node (ref "U1") (pin "AK14") (pinfunction "P0.18/QPSI_CS_AK14") (pintype "bidirectional"))
    )
    (net (code "69") (name "unconnected-(U1C-P0.20-PadAK16)") (class "Default")
      (node (ref "U1") (pin "AK16") (pinfunction "P0.20_AK16") (pintype "bidirectional"))
    )
    (net (code "70") (name "unconnected-(U1C-P0.22-PadAK18)") (class "Default")
      (node (ref "U1") (pin "AK18") (pinfunction "P0.22_AK18") (pintype "bidirectional"))
    )
    (net (code "71") (name "unconnected-(U1C-P0.23-PadAK20)") (class "Default")
      (node (ref "U1") (pin "AK20") (pinfunction "P0.23_AK20") (pintype "bidirectional"))
    )
    (net (code "72") (name "unconnected-(U1C-P0.24-PadAL27)") (class "Default")
      (node (ref "U1") (pin "AL27") (pinfunction "P0.24_AL27") (pintype "bidirectional"))
    )
    (net (code "73") (name "unconnected-(U1C-P0.25{slash}AIN4-PadAK28)") (class "Default")
      (node (ref "U1") (pin "AK28") (pinfunction "P0.25/AIN4_AK28") (pintype "bidirectional"))
    )
    (net (code "74") (name "unconnected-(U1C-P0.26{slash}AIN5-PadAL29)") (class "Default")
      (node (ref "U1") (pin "AL29") (pinfunction "P0.26/AIN5_AL29") (pintype "bidirectional"))
    )
    (net (code "75") (name "unconnected-(U1C-P0.27{slash}AIN6-PadAK30)") (class "Default")
      (node (ref "U1") (pin "AK30") (pinfunction "P0.27/AIN6_AK30") (pintype "bidirectional"))
    )
    (net (code "76") (name "unconnected-(U1C-P0.28{slash}AIN7-PadAE31)") (class "Default")
      (node (ref "U1") (pin "AE31") (pinfunction "P0.28/AIN7_AE31") (pintype "bidirectional"))
    )
    (net (code "77") (name "unconnected-(U1C-P0.29-PadU31)") (class "Default")
      (node (ref "U1") (pin "U31") (pinfunction "P0.29_U31") (pintype "bidirectional"))
    )
    (net (code "78") (name "unconnected-(U1C-P0.30-PadB24)") (class "Default")
      (node (ref "U1") (pin "B24") (pinfunction "P0.30_B24") (pintype "bidirectional"))
    )
    (net (code "79") (name "unconnected-(U1C-P0.31-PadB22)") (class "Default")
      (node (ref "U1") (pin "B22") (pinfunction "P0.31_B22") (pintype "bidirectional"))
    )
    (net (code "80") (name "unconnected-(U1D-D+-PadB2)") (class "Default")
      (node (ref "U1") (pin "B2") (pinfunction "D+_B2") (pintype "bidirectional"))
    )
    (net (code "81") (name "unconnected-(U1D-D--PadB4)") (class "Default")
      (node (ref "U1") (pin "B4") (pinfunction "D-_B4") (pintype "bidirectional"))
    )
    (net (code "82") (name "unconnected-(U2-N.C.-Pad14)") (class "Default")
      (node (ref "U2") (pin "14") (pinfunction "N.C._14") (pintype "no_connect"))
    )
    (net (code "83") (name "unconnected-(U2-N.C._2-Pad1)") (class "Default")
      (node (ref "U2") (pin "1") (pinfunction "N.C._2_1") (pintype "no_connect"))
    )
    (net (code "84") (name "unconnected-(U2-N.C._3-Pad5)") (class "Default")
      (node (ref "U2") (pin "5") (pinfunction "N.C._3_5") (pintype "no_connect"))
    )
    (net (code "85") (name "unconnected-(U2-N.C._4-Pad6)") (class "Default")
      (node (ref "U2") (pin "6") (pinfunction "N.C._4_6") (pintype "no_connect"))
    )
    (net (code "86") (name "unconnected-(U2-N.C._5-Pad7)") (class "Default")
      (node (ref "U2") (pin "7") (pinfunction "N.C._5_7") (pintype "no_connect"))
    )
    (net (code "87") (name "unconnected-(U2-N.C._6-Pad8)") (class "Default")
      (node (ref "U2") (pin "8") (pinfunction "N.C._6_8") (pintype "no_connect"))
    )
    (net (code "88") (name "unconnected-(U4-P4-Pad4)") (class "Default")
      (node (ref "U4") (pin "4") (pinfunction "P4_4") (pintype "bidirectional"))
    )
    (net (code "89") (name "unconnected-(U5-32KIN-Pad9)") (class "Default")
      (node (ref "U5") (pin "9") (pinfunction "32KIN_9") (pintype "input"))
    )
    (net (code "90") (name "unconnected-(U5-32KOUT-Pad8)") (class "Default")
      (node (ref "U5") (pin "8") (pinfunction "32KOUT_8") (pintype "output"))
    )
    (net (code "91") (name "unconnected-(U5-ACCEL_INT-Pad19)") (class "Default")
      (node (ref "U5") (pin "19") (pinfunction "ACCEL_INT_19") (pintype "input"))
    )
    (net (code "92") (name "unconnected-(U5-D.N.C.-Pad21)") (class "Default")
      (node (ref "U5") (pin "21") (pinfunction "D.N.C._21") (pintype "no_connect"))
    )
    (net (code "93") (name "unconnected-(U5-D.N.C._2-Pad2)") (class "Default")
      (node (ref "U5") (pin "2") (pinfunction "D.N.C._2_2") (pintype "no_connect"))
    )
    (net (code "94") (name "unconnected-(U5-D.N.C._3-Pad4)") (class "Default")
      (node (ref "U5") (pin "4") (pinfunction "D.N.C._3_4") (pintype "no_connect"))
    )
    (net (code "95") (name "unconnected-(U5-D.N.C._4-Pad5)") (class "Default")
      (node (ref "U5") (pin "5") (pinfunction "D.N.C._4_5") (pintype "no_connect"))
    )
    (net (code "96") (name "unconnected-(U5-D.N.C._5-Pad16)") (class "Default")
      (node (ref "U5") (pin "16") (pinfunction "D.N.C._5_16") (pintype "no_connect"))
    )
    (net (code "97") (name "unconnected-(U5-D.N.C._6-Pad17)") (class "Default")
      (node (ref "U5") (pin "17") (pinfunction "D.N.C._6_17") (pintype "no_connect"))
    )
    (net (code "98") (name "unconnected-(U5-D.N.C._7-Pad20)") (class "Default")
      (node (ref "U5") (pin "20") (pinfunction "D.N.C._7_20") (pintype "no_connect"))
    )
    (net (code "99") (name "unconnected-(U5-HR_INT-Pad18)") (class "Default")
      (node (ref "U5") (pin "18") (pinfunction "HR_INT_18") (pintype "input"))
    )
    (net (code "100") (name "unconnected-(U5-MFIO-Pad1)") (class "Default")
      (node (ref "U5") (pin "1") (pinfunction "MFIO_1") (pintype "bidirectional"))
    )
    (net (code "101") (name "unconnected-(U5-N.C.-Pad15)") (class "Default")
      (node (ref "U5") (pin "15") (pinfunction "N.C._15") (pintype "no_connect"))
    )
    (net (code "102") (name "unconnected-(U5-N.C._2-Pad3)") (class "Default")
      (node (ref "U5") (pin "3") (pinfunction "N.C._2_3") (pintype "no_connect"))
    )
    (net (code "103") (name "unconnected-(U5-RSTN-Pad6)") (class "Default")
      (node (ref "U5") (pin "6") (pinfunction "RSTN_6") (pintype "input"))
    )
    (net (code "104") (name "unconnected-(U5-SENSOR_SCL-Pad14)") (class "Default")
      (node (ref "U5") (pin "14") (pinfunction "SENSOR_SCL_14") (pintype "passive"))
    )
    (net (code "105") (name "unconnected-(U5-SENSOR_SDA-Pad13)") (class "Default")
      (node (ref "U5") (pin "13") (pinfunction "SENSOR_SDA_13") (pintype "passive"))
    )
    (net (code "106") (name "unconnected-(U5-SLAVE_SCL-Pad24)") (class "Default")
      (node (ref "U5") (pin "24") (pinfunction "SLAVE_SCL_24") (pintype "passive"))
    )
    (net (code "107") (name "unconnected-(U5-SLAVE_SDA-Pad23)") (class "Default")
      (node (ref "U5") (pin "23") (pinfunction "SLAVE_SDA_23") (pintype "passive"))
    )
  )
)
